# LED.net
KiCad netlist of a schematic drawn in Altium Designer
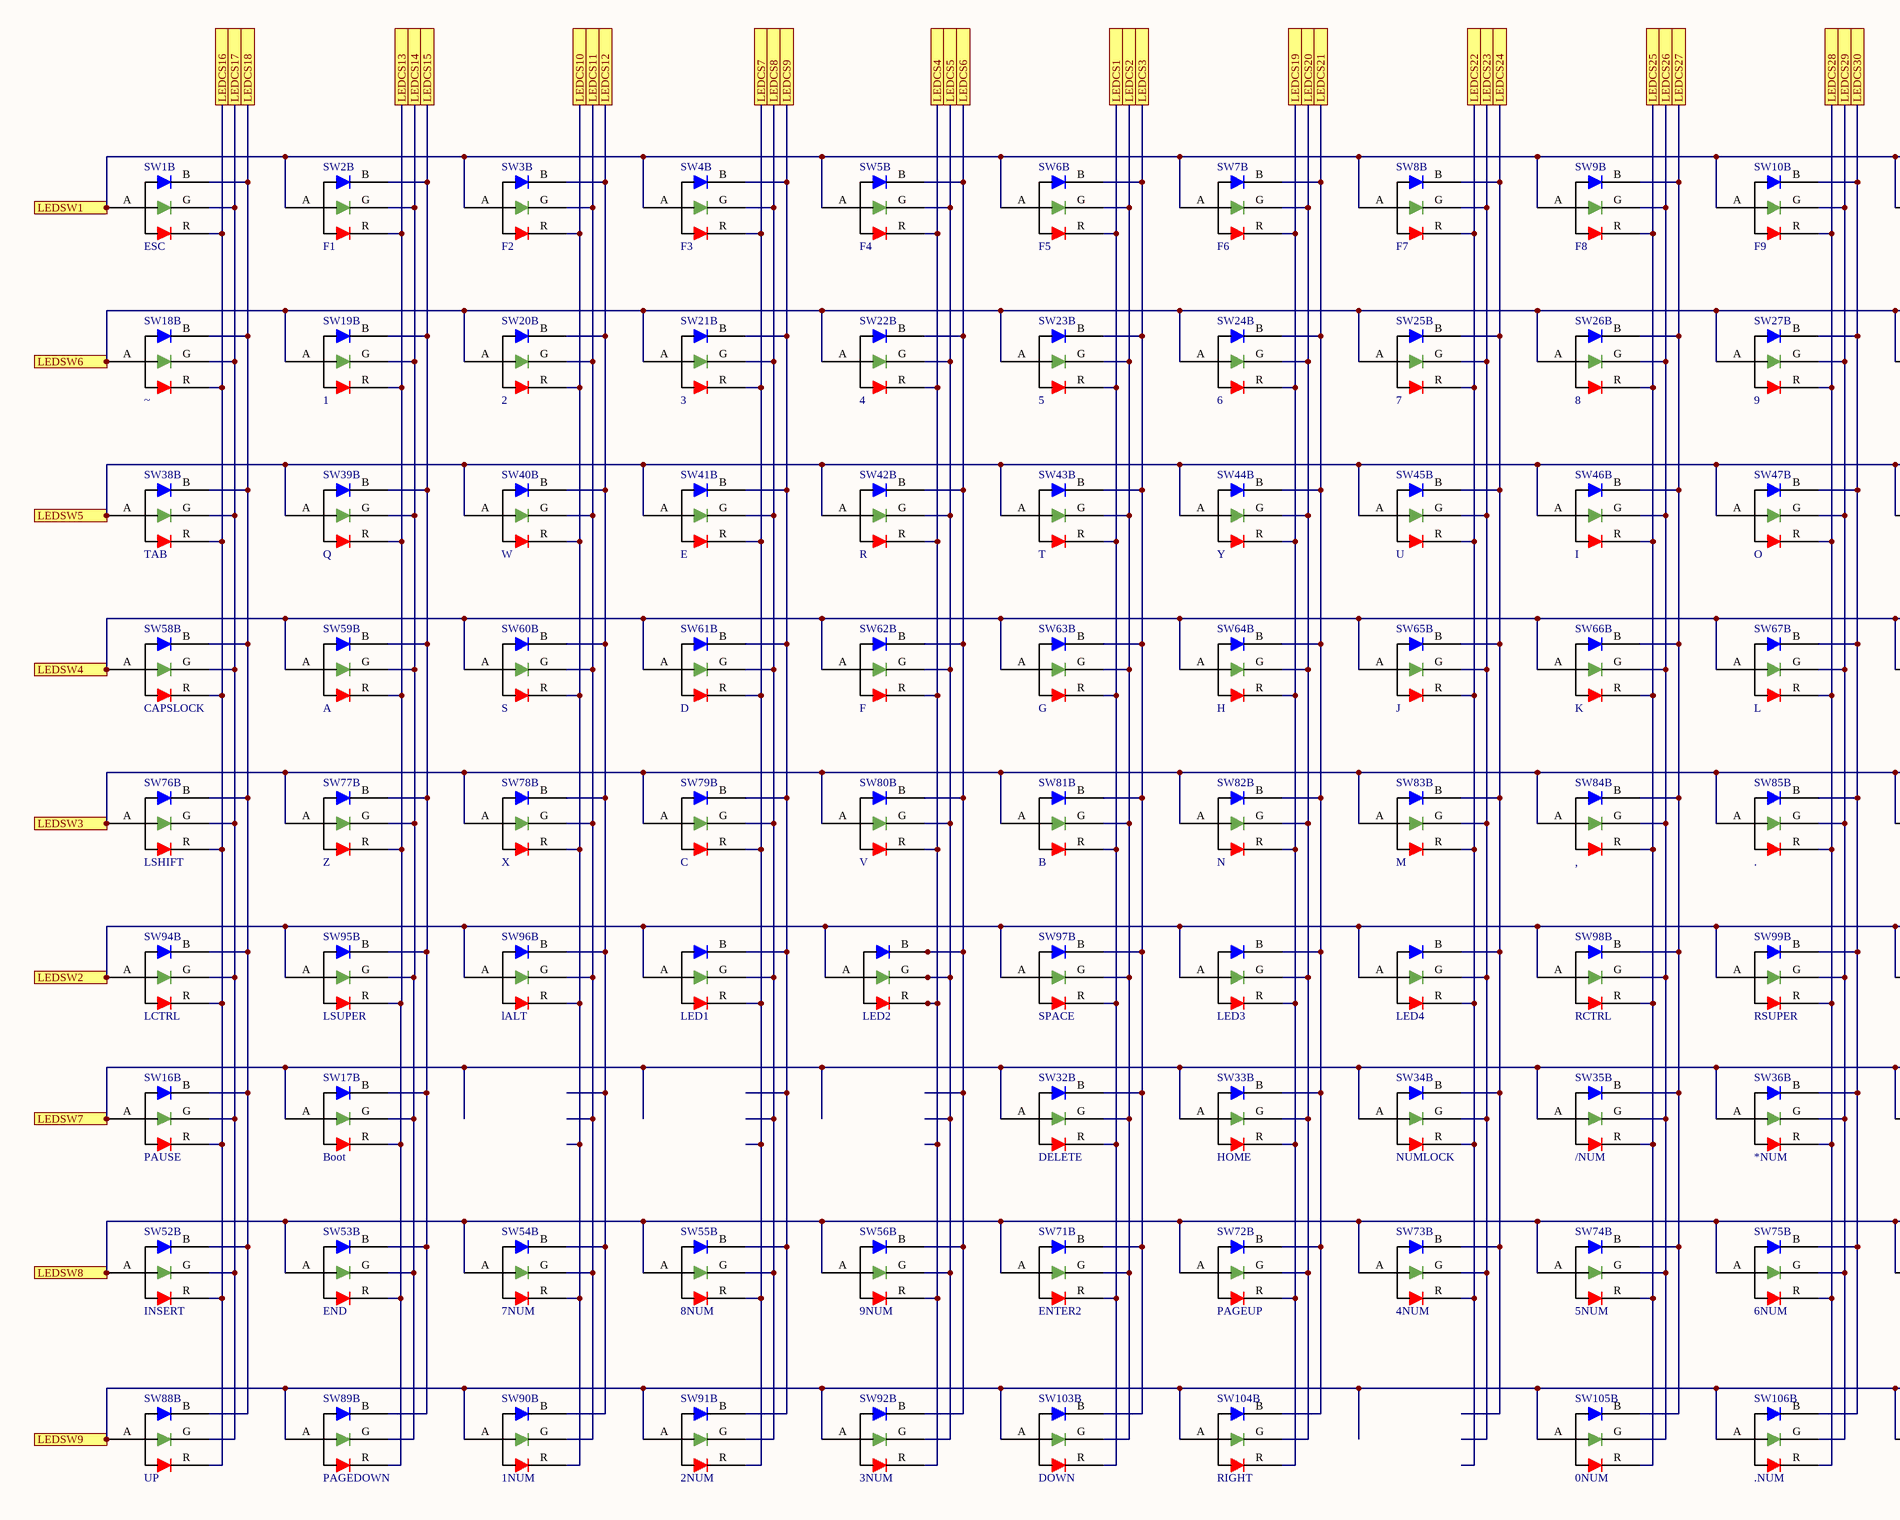
[diagram p0: LED.SchDoc, left]
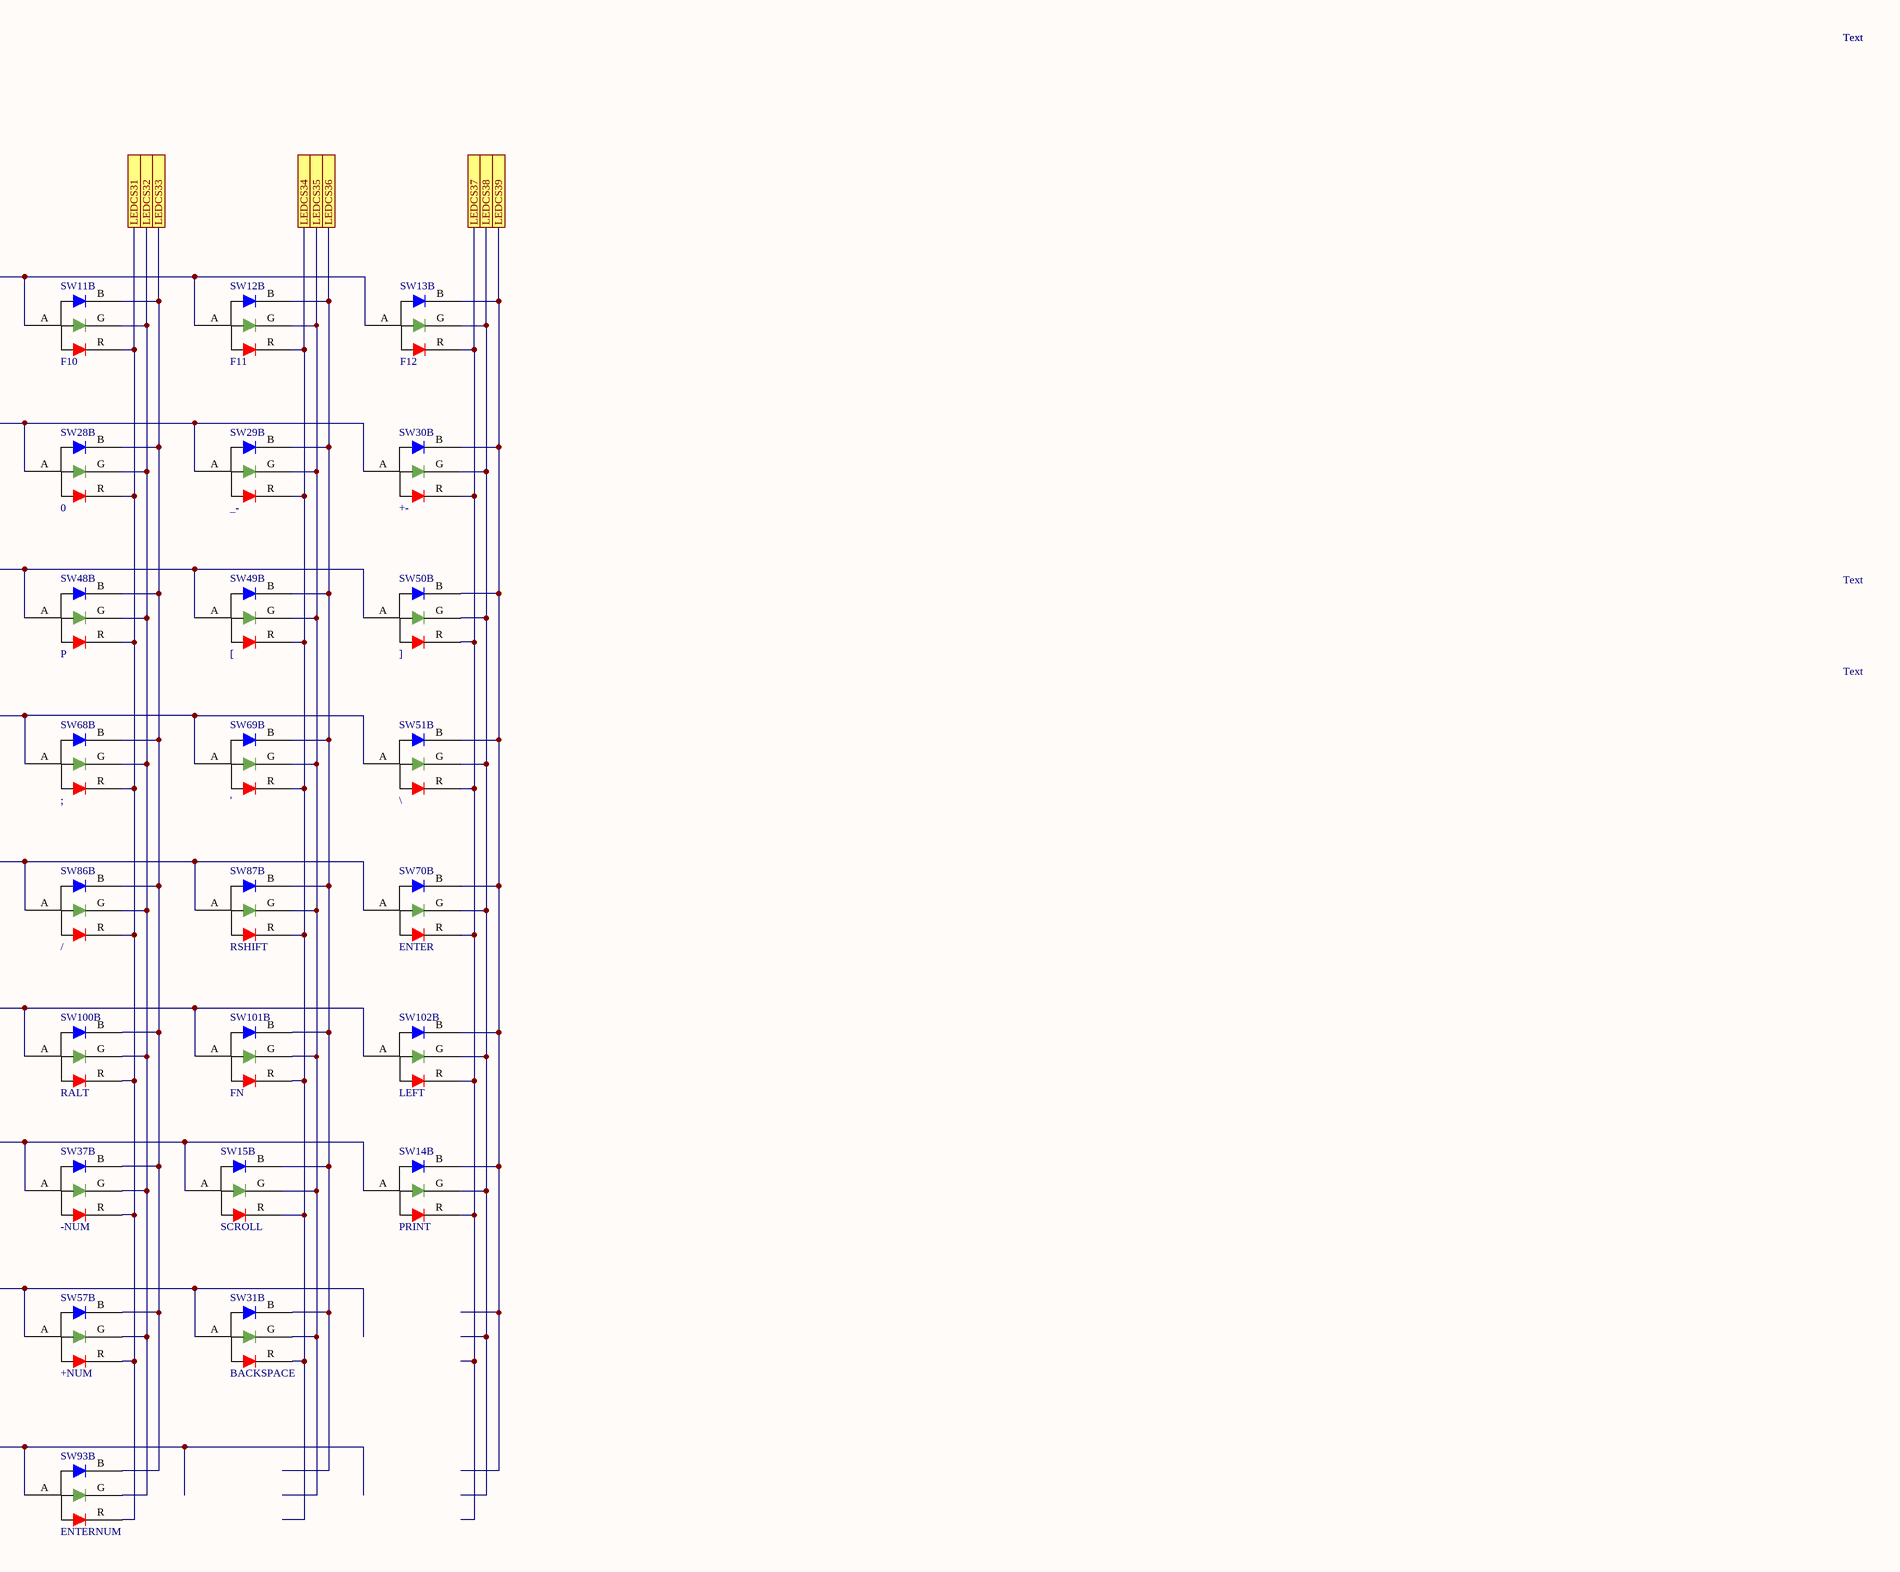
[diagram p1: LED.SchDoc, right]

(export (version "E")
  (design (tool "Eeschema 10.0.6"))
  (components
    (comp (ref "LED1")
      (value "ASMB-MTB0-0A3A2")
      (footprint "smd led")
      (libsource (lib "General") (part "ASMB-MTB0-0A3A2"))
    )
    (comp (ref "LED2")
      (value "ASMB-MTB0-0A3A2")
      (footprint "smd led")
      (libsource (lib "General") (part "ASMB-MTB0-0A3A2"))
    )
    (comp (ref "LED3")
      (value "ASMB-MTB0-0A3A2")
      (footprint "smd led")
      (libsource (lib "General") (part "ASMB-MTB0-0A3A2"))
    )
    (comp (ref "LED4")
      (value "ASMB-MTB0-0A3A2")
      (footprint "smd led")
      (libsource (lib "General") (part "ASMB-MTB0-0A3A2"))
    )
    (comp (ref "SW1")
      (value "ESC")
      (footprint "SWITCH_U1_W_LED")
      (libsource (lib "General") (part "MX_SWITCH_SINGLE_W_SMD_LED"))
    )
    (comp (ref "SW2")
      (value "F1")
      (footprint "SWITCH_U1_W_LED")
      (libsource (lib "General") (part "MX_SWITCH_SINGLE_W_SMD_LED"))
    )
    (comp (ref "SW3")
      (value "F2")
      (footprint "SWITCH_U1_W_LED")
      (libsource (lib "General") (part "MX_SWITCH_SINGLE_W_SMD_LED"))
    )
    (comp (ref "SW4")
      (value "F3")
      (footprint "SWITCH_U1_W_LED")
      (libsource (lib "General") (part "MX_SWITCH_SINGLE_W_SMD_LED"))
    )
    (comp (ref "SW5")
      (value "F4")
      (footprint "SWITCH_U1_W_LED")
      (libsource (lib "General") (part "MX_SWITCH_SINGLE_W_SMD_LED"))
    )
    (comp (ref "SW6")
      (value "F5")
      (footprint "SWITCH_U1_W_LED")
      (libsource (lib "General") (part "MX_SWITCH_SINGLE_W_SMD_LED"))
    )
    (comp (ref "SW7")
      (value "F6")
      (footprint "SWITCH_U1_W_LED")
      (libsource (lib "General") (part "MX_SWITCH_SINGLE_W_SMD_LED"))
    )
    (comp (ref "SW8")
      (value "F7")
      (footprint "SWITCH_U1_W_LED")
      (libsource (lib "General") (part "MX_SWITCH_SINGLE_W_SMD_LED"))
    )
    (comp (ref "SW9")
      (value "F8")
      (footprint "SWITCH_U1_W_LED")
      (libsource (lib "General") (part "MX_SWITCH_SINGLE_W_SMD_LED"))
    )
    (comp (ref "SW10")
      (value "F9")
      (footprint "SWITCH_U1_W_LED")
      (libsource (lib "General") (part "MX_SWITCH_SINGLE_W_SMD_LED"))
    )
    (comp (ref "SW11")
      (value "F10")
      (footprint "SWITCH_U1_W_LED")
      (libsource (lib "General") (part "MX_SWITCH_SINGLE_W_SMD_LED"))
    )
    (comp (ref "SW12")
      (value "F11")
      (footprint "SWITCH_U1_W_LED")
      (libsource (lib "General") (part "MX_SWITCH_SINGLE_W_SMD_LED"))
    )
    (comp (ref "SW13")
      (value "F12")
      (footprint "SWITCH_U1_W_LED")
      (libsource (lib "General") (part "MX_SWITCH_SINGLE_W_SMD_LED"))
    )
    (comp (ref "SW14")
      (value "PRINT")
      (footprint "SWITCH_U1_W_LED")
      (libsource (lib "General") (part "MX_SWITCH_SINGLE_W_SMD_LED"))
    )
    (comp (ref "SW15")
      (value "SCROLL")
      (footprint "SWITCH_U1_W_LED")
      (libsource (lib "General") (part "MX_SWITCH_SINGLE_W_SMD_LED"))
    )
    (comp (ref "SW16")
      (value "PAUSE")
      (footprint "SWITCH_U1_W_LED")
      (libsource (lib "General") (part "MX_SWITCH_SINGLE_W_SMD_LED"))
    )
    (comp (ref "SW17")
      (value "Boot")
      (footprint "SWITCH_U1_W_LED")
      (libsource (lib "General") (part "MX_SWITCH_SINGLE_W_SMD_LED"))
    )
    (comp (ref "SW18")
      (value "~")
      (footprint "SWITCH_U1_W_LED")
      (libsource (lib "General") (part "MX_SWITCH_SINGLE_W_SMD_LED"))
    )
    (comp (ref "SW19")
      (value "1")
      (footprint "SWITCH_U1_W_LED")
      (libsource (lib "General") (part "MX_SWITCH_SINGLE_W_SMD_LED"))
    )
    (comp (ref "SW20")
      (value "2")
      (footprint "SWITCH_U1_W_LED")
      (libsource (lib "General") (part "MX_SWITCH_SINGLE_W_SMD_LED"))
    )
    (comp (ref "SW21")
      (value "3")
      (footprint "SWITCH_U1_W_LED")
      (libsource (lib "General") (part "MX_SWITCH_SINGLE_W_SMD_LED"))
    )
    (comp (ref "SW22")
      (value "4")
      (footprint "SWITCH_U1_W_LED")
      (libsource (lib "General") (part "MX_SWITCH_SINGLE_W_SMD_LED"))
    )
    (comp (ref "SW23")
      (value "5")
      (footprint "SWITCH_U1_W_LED")
      (libsource (lib "General") (part "MX_SWITCH_SINGLE_W_SMD_LED"))
    )
    (comp (ref "SW24")
      (value "6")
      (footprint "SWITCH_U1_W_LED")
      (libsource (lib "General") (part "MX_SWITCH_SINGLE_W_SMD_LED"))
    )
    (comp (ref "SW25")
      (value "7")
      (footprint "SWITCH_U1_W_LED")
      (libsource (lib "General") (part "MX_SWITCH_SINGLE_W_SMD_LED"))
    )
    (comp (ref "SW26")
      (value "8")
      (footprint "SWITCH_U1_W_LED")
      (libsource (lib "General") (part "MX_SWITCH_SINGLE_W_SMD_LED"))
    )
    (comp (ref "SW27")
      (value "9")
      (footprint "SWITCH_U1_W_LED")
      (libsource (lib "General") (part "MX_SWITCH_SINGLE_W_SMD_LED"))
    )
    (comp (ref "SW28")
      (value "0")
      (footprint "SWITCH_U1_W_LED")
      (libsource (lib "General") (part "MX_SWITCH_SINGLE_W_SMD_LED"))
    )
    (comp (ref "SW29")
      (value "_-")
      (footprint "SWITCH_U1_W_LED")
      (libsource (lib "General") (part "MX_SWITCH_SINGLE_W_SMD_LED"))
    )
    (comp (ref "SW30")
      (value "+-")
      (footprint "SWITCH_U1_W_LED")
      (libsource (lib "General") (part "MX_SWITCH_SINGLE_W_SMD_LED"))
    )
    (comp (ref "SW31")
      (value "BACKSPACE")
      (footprint "SWITCH_U2_W_LED")
      (libsource (lib "General") (part "MX_SWITCH_SINGLE_W_SMD_LED"))
    )
    (comp (ref "SW32")
      (value "DELETE")
      (footprint "SWITCH_U1_W_LED")
      (libsource (lib "General") (part "MX_SWITCH_SINGLE_W_SMD_LED"))
    )
    (comp (ref "SW33")
      (value "HOME")
      (footprint "SWITCH_U1_W_LED")
      (libsource (lib "General") (part "MX_SWITCH_SINGLE_W_SMD_LED"))
    )
    (comp (ref "SW34")
      (value "NUMLOCK")
      (footprint "SWITCH_U1_W_LED")
      (libsource (lib "General") (part "MX_SWITCH_SINGLE_W_SMD_LED"))
    )
    (comp (ref "SW35")
      (value "/NUM")
      (footprint "SWITCH_U1_W_LED")
      (libsource (lib "General") (part "MX_SWITCH_SINGLE_W_SMD_LED"))
    )
    (comp (ref "SW36")
      (value "*NUM")
      (footprint "SWITCH_U1_W_LED")
      (libsource (lib "General") (part "MX_SWITCH_SINGLE_W_SMD_LED"))
    )
    (comp (ref "SW37")
      (value "-NUM")
      (footprint "SWITCH_U1_W_LED")
      (libsource (lib "General") (part "MX_SWITCH_SINGLE_W_SMD_LED"))
    )
    (comp (ref "SW38")
      (value "TAB")
      (footprint "SWITCH_U1.50_W_LED")
      (libsource (lib "General") (part "MX_SWITCH_SINGLE_W_SMD_LED"))
    )
    (comp (ref "SW39")
      (value "Q")
      (footprint "SWITCH_U1_W_LED")
      (libsource (lib "General") (part "MX_SWITCH_SINGLE_W_SMD_LED"))
    )
    (comp (ref "SW40")
      (value "W")
      (footprint "SWITCH_U1_W_LED")
      (libsource (lib "General") (part "MX_SWITCH_SINGLE_W_SMD_LED"))
    )
    (comp (ref "SW41")
      (value "E")
      (footprint "SWITCH_U1_W_LED")
      (libsource (lib "General") (part "MX_SWITCH_SINGLE_W_SMD_LED"))
    )
    (comp (ref "SW42")
      (value "R")
      (footprint "SWITCH_U1_W_LED")
      (libsource (lib "General") (part "MX_SWITCH_SINGLE_W_SMD_LED"))
    )
    (comp (ref "SW43")
      (value "T")
      (footprint "SWITCH_U1_W_LED")
      (libsource (lib "General") (part "MX_SWITCH_SINGLE_W_SMD_LED"))
    )
    (comp (ref "SW44")
      (value "Y")
      (footprint "SWITCH_U1_W_LED")
      (libsource (lib "General") (part "MX_SWITCH_SINGLE_W_SMD_LED"))
    )
    (comp (ref "SW45")
      (value "U")
      (footprint "SWITCH_U1_W_LED")
      (libsource (lib "General") (part "MX_SWITCH_SINGLE_W_SMD_LED"))
    )
    (comp (ref "SW46")
      (value "I")
      (footprint "SWITCH_U1_W_LED")
      (libsource (lib "General") (part "MX_SWITCH_SINGLE_W_SMD_LED"))
    )
    (comp (ref "SW47")
      (value "O")
      (footprint "SWITCH_U1_W_LED")
      (libsource (lib "General") (part "MX_SWITCH_SINGLE_W_SMD_LED"))
    )
    (comp (ref "SW48")
      (value "P")
      (footprint "SWITCH_U1_W_LED")
      (libsource (lib "General") (part "MX_SWITCH_SINGLE_W_SMD_LED"))
    )
    (comp (ref "SW49")
      (value "[")
      (footprint "SWITCH_U1_W_LED")
      (libsource (lib "General") (part "MX_SWITCH_SINGLE_W_SMD_LED"))
    )
    (comp (ref "SW50")
      (value "]")
      (footprint "SWITCH_U1_W_LED")
      (libsource (lib "General") (part "MX_SWITCH_SINGLE_W_SMD_LED"))
    )
    (comp (ref "SW51")
      (value "\\")
      (footprint "SWITCH_U1.50_W_LED")
      (libsource (lib "General") (part "MX_SWITCH_SINGLE_W_SMD_LED"))
    )
    (comp (ref "SW52")
      (value "INSERT")
      (footprint "SWITCH_U1_W_LED")
      (libsource (lib "General") (part "MX_SWITCH_SINGLE_W_SMD_LED"))
    )
    (comp (ref "SW53")
      (value "END")
      (footprint "SWITCH_U1_W_LED")
      (libsource (lib "General") (part "MX_SWITCH_SINGLE_W_SMD_LED"))
    )
    (comp (ref "SW54")
      (value "7NUM")
      (footprint "SWITCH_U1_W_LED")
      (libsource (lib "General") (part "MX_SWITCH_SINGLE_W_SMD_LED"))
    )
    (comp (ref "SW55")
      (value "8NUM")
      (footprint "SWITCH_U1_W_LED")
      (libsource (lib "General") (part "MX_SWITCH_SINGLE_W_SMD_LED"))
    )
    (comp (ref "SW56")
      (value "9NUM")
      (footprint "SWITCH_U1_W_LED")
      (libsource (lib "General") (part "MX_SWITCH_SINGLE_W_SMD_LED"))
    )
    (comp (ref "SW57")
      (value "+NUM")
      (footprint "SWITCH_U2_W_LED - vert")
      (libsource (lib "General") (part "MX_SWITCH_SINGLE_W_SMD_LED"))
    )
    (comp (ref "SW58")
      (value "CAPSLOCK")
      (footprint "SWITCH_U1.75_W_LED")
      (libsource (lib "General") (part "MX_SWITCH_SINGLE_W_SMD_LED"))
    )
    (comp (ref "SW59")
      (value "A")
      (footprint "SWITCH_U1_W_LED")
      (libsource (lib "General") (part "MX_SWITCH_SINGLE_W_SMD_LED"))
    )
    (comp (ref "SW60")
      (value "S")
      (footprint "SWITCH_U1_W_LED")
      (libsource (lib "General") (part "MX_SWITCH_SINGLE_W_SMD_LED"))
    )
    (comp (ref "SW61")
      (value "D")
      (footprint "SWITCH_U1_W_LED")
      (libsource (lib "General") (part "MX_SWITCH_SINGLE_W_SMD_LED"))
    )
    (comp (ref "SW62")
      (value "F")
      (footprint "SWITCH_U1_W_LED")
      (libsource (lib "General") (part "MX_SWITCH_SINGLE_W_SMD_LED"))
    )
    (comp (ref "SW63")
      (value "G")
      (footprint "SWITCH_U1_W_LED")
      (libsource (lib "General") (part "MX_SWITCH_SINGLE_W_SMD_LED"))
    )
    (comp (ref "SW64")
      (value "H")
      (footprint "SWITCH_U1_W_LED")
      (libsource (lib "General") (part "MX_SWITCH_SINGLE_W_SMD_LED"))
    )
    (comp (ref "SW65")
      (value "J")
      (footprint "SWITCH_U1_W_LED")
      (libsource (lib "General") (part "MX_SWITCH_SINGLE_W_SMD_LED"))
    )
    (comp (ref "SW66")
      (value "K")
      (footprint "SWITCH_U1_W_LED")
      (libsource (lib "General") (part "MX_SWITCH_SINGLE_W_SMD_LED"))
    )
    (comp (ref "SW67")
      (value "L")
      (footprint "SWITCH_U1_W_LED")
      (libsource (lib "General") (part "MX_SWITCH_SINGLE_W_SMD_LED"))
    )
    (comp (ref "SW68")
      (value ";")
      (footprint "SWITCH_U1_W_LED")
      (libsource (lib "General") (part "MX_SWITCH_SINGLE_W_SMD_LED"))
    )
    (comp (ref "SW69")
      (value "'")
      (footprint "SWITCH_U1_W_LED")
      (libsource (lib "General") (part "MX_SWITCH_SINGLE_W_SMD_LED"))
    )
    (comp (ref "SW70")
      (value "ENTER")
      (footprint "SWITCH_U2.25_W_LED")
      (libsource (lib "General") (part "MX_SWITCH_SINGLE_W_SMD_LED"))
    )
    (comp (ref "SW71")
      (value "ENTER2")
      (footprint "SWITCH_U1_W_LED")
      (libsource (lib "General") (part "MX_SWITCH_SINGLE_W_SMD_LED"))
    )
    (comp (ref "SW72")
      (value "PAGEUP")
      (footprint "SWITCH_U1_W_LED")
      (libsource (lib "General") (part "MX_SWITCH_SINGLE_W_SMD_LED"))
    )
    (comp (ref "SW73")
      (value "4NUM")
      (footprint "SWITCH_U1_W_LED")
      (libsource (lib "General") (part "MX_SWITCH_SINGLE_W_SMD_LED"))
    )
    (comp (ref "SW74")
      (value "5NUM")
      (footprint "SWITCH_U1_W_LED")
      (libsource (lib "General") (part "MX_SWITCH_SINGLE_W_SMD_LED"))
    )
    (comp (ref "SW75")
      (value "6NUM")
      (footprint "SWITCH_U1_W_LED")
      (libsource (lib "General") (part "MX_SWITCH_SINGLE_W_SMD_LED"))
    )
    (comp (ref "SW76")
      (value "LSHIFT")
      (footprint "SWITCH_U2.25_W_LED")
      (libsource (lib "General") (part "MX_SWITCH_SINGLE_W_SMD_LED"))
    )
    (comp (ref "SW77")
      (value "Z")
      (footprint "SWITCH_U1_W_LED")
      (libsource (lib "General") (part "MX_SWITCH_SINGLE_W_SMD_LED"))
    )
    (comp (ref "SW78")
      (value "X")
      (footprint "SWITCH_U1_W_LED")
      (libsource (lib "General") (part "MX_SWITCH_SINGLE_W_SMD_LED"))
    )
    (comp (ref "SW79")
      (value "C")
      (footprint "SWITCH_U1_W_LED")
      (libsource (lib "General") (part "MX_SWITCH_SINGLE_W_SMD_LED"))
    )
    (comp (ref "SW80")
      (value "V")
      (footprint "SWITCH_U1_W_LED")
      (libsource (lib "General") (part "MX_SWITCH_SINGLE_W_SMD_LED"))
    )
    (comp (ref "SW81")
      (value "B")
      (footprint "SWITCH_U1_W_LED")
      (libsource (lib "General") (part "MX_SWITCH_SINGLE_W_SMD_LED"))
    )
    (comp (ref "SW82")
      (value "N")
      (footprint "SWITCH_U1_W_LED")
      (libsource (lib "General") (part "MX_SWITCH_SINGLE_W_SMD_LED"))
    )
    (comp (ref "SW83")
      (value "M")
      (footprint "SWITCH_U1_W_LED")
      (libsource (lib "General") (part "MX_SWITCH_SINGLE_W_SMD_LED"))
    )
    (comp (ref "SW84")
      (value ",")
      (footprint "SWITCH_U1_W_LED")
      (libsource (lib "General") (part "MX_SWITCH_SINGLE_W_SMD_LED"))
    )
    (comp (ref "SW85")
      (value ".")
      (footprint "SWITCH_U1_W_LED")
      (libsource (lib "General") (part "MX_SWITCH_SINGLE_W_SMD_LED"))
    )
    (comp (ref "SW86")
      (value "/")
      (footprint "SWITCH_U1_W_LED")
      (libsource (lib "General") (part "MX_SWITCH_SINGLE_W_SMD_LED"))
    )
    (comp (ref "SW87")
      (value "RSHIFT")
      (footprint "SWITCH_U2.75_W_LED")
      (libsource (lib "General") (part "MX_SWITCH_SINGLE_W_SMD_LED"))
    )
    (comp (ref "SW88")
      (value "UP")
      (footprint "SWITCH_U1_W_LED")
      (libsource (lib "General") (part "MX_SWITCH_SINGLE_W_SMD_LED"))
    )
    (comp (ref "SW89")
      (value "PAGEDOWN")
      (footprint "SWITCH_U1_W_LED")
      (libsource (lib "General") (part "MX_SWITCH_SINGLE_W_SMD_LED"))
    )
    (comp (ref "SW90")
      (value "1NUM")
      (footprint "SWITCH_U1_W_LED")
      (libsource (lib "General") (part "MX_SWITCH_SINGLE_W_SMD_LED"))
    )
    (comp (ref "SW91")
      (value "2NUM")
      (footprint "SWITCH_U1_W_LED")
      (libsource (lib "General") (part "MX_SWITCH_SINGLE_W_SMD_LED"))
    )
    (comp (ref "SW92")
      (value "3NUM")
      (footprint "SWITCH_U1_W_LED")
      (libsource (lib "General") (part "MX_SWITCH_SINGLE_W_SMD_LED"))
    )
    (comp (ref "SW93")
      (value "ENTERNUM")
      (footprint "SWITCH_U2_W_LED - vert")
      (libsource (lib "General") (part "MX_SWITCH_SINGLE_W_SMD_LED"))
    )
    (comp (ref "SW94")
      (value "LCTRL")
      (footprint "SWITCH_U1.25_W_LED")
      (libsource (lib "General") (part "MX_SWITCH_SINGLE_W_SMD_LED"))
    )
    (comp (ref "SW95")
      (value "LSUPER")
      (footprint "SWITCH_U1.25_W_LED")
      (libsource (lib "General") (part "MX_SWITCH_SINGLE_W_SMD_LED"))
    )
    (comp (ref "SW96")
      (value "lALT")
      (footprint "SWITCH_U1.25_W_LED")
      (libsource (lib "General") (part "MX_SWITCH_SINGLE_W_SMD_LED"))
    )
    (comp (ref "SW97")
      (value "SPACE")
      (footprint "SWITCH_U6.25_W_LED - duplicate")
      (libsource (lib "General") (part "MX_SWITCH_SINGLE_W_SMD_LED"))
    )
    (comp (ref "SW98")
      (value "RCTRL")
      (footprint "SWITCH_U1_W_LED")
      (libsource (lib "General") (part "MX_SWITCH_SINGLE_W_SMD_LED"))
    )
    (comp (ref "SW99")
      (value "RSUPER")
      (footprint "SWITCH_U1_W_LED")
      (libsource (lib "General") (part "MX_SWITCH_SINGLE_W_SMD_LED"))
    )
    (comp (ref "SW100")
      (value "RALT")
      (footprint "SWITCH_U1_W_LED")
      (libsource (lib "General") (part "MX_SWITCH_SINGLE_W_SMD_LED"))
    )
    (comp (ref "SW101")
      (value "FN")
      (footprint "SWITCH_U1_W_LED")
      (libsource (lib "General") (part "MX_SWITCH_SINGLE_W_SMD_LED"))
    )
    (comp (ref "SW102")
      (value "LEFT")
      (footprint "SWITCH_U1_W_LED")
      (libsource (lib "General") (part "MX_SWITCH_SINGLE_W_SMD_LED"))
    )
    (comp (ref "SW103")
      (value "DOWN")
      (footprint "SWITCH_U1_W_LED")
      (libsource (lib "General") (part "MX_SWITCH_SINGLE_W_SMD_LED"))
    )
    (comp (ref "SW104")
      (value "RIGHT")
      (footprint "SWITCH_U1_W_LED")
      (libsource (lib "General") (part "MX_SWITCH_SINGLE_W_SMD_LED"))
    )
    (comp (ref "SW105")
      (value "0NUM")
      (footprint "SWITCH_U2_W_LED")
      (libsource (lib "General") (part "MX_SWITCH_SINGLE_W_SMD_LED"))
    )
    (comp (ref "SW106")
      (value ".NUM")
      (footprint "SWITCH_U1_W_LED")
      (libsource (lib "General") (part "MX_SWITCH_SINGLE_W_SMD_LED"))
    )
  )
  (nets
    (net (code "1") (name "/LEDCS1") (class "Default")
      (node (ref "SW103") (pin "R") (pinfunction "R_R") (pintype "passive"))
      (node (ref "SW23") (pin "R") (pinfunction "R_R") (pintype "passive"))
      (node (ref "SW32") (pin "R") (pinfunction "R_R") (pintype "passive"))
      (node (ref "SW43") (pin "R") (pinfunction "R_R") (pintype "passive"))
      (node (ref "SW6") (pin "R") (pinfunction "R_R") (pintype "passive"))
      (node (ref "SW63") (pin "R") (pinfunction "R_R") (pintype "passive"))
      (node (ref "SW71") (pin "R") (pinfunction "R_R") (pintype "passive"))
      (node (ref "SW81") (pin "R") (pinfunction "R_R") (pintype "passive"))
      (node (ref "SW97") (pin "R") (pinfunction "R_R") (pintype "passive"))
    )
    (net (code "2") (name "/LEDCS2") (class "Default")
      (node (ref "SW103") (pin "G") (pinfunction "G_G") (pintype "passive"))
      (node (ref "SW23") (pin "G") (pinfunction "G_G") (pintype "passive"))
      (node (ref "SW32") (pin "G") (pinfunction "G_G") (pintype "passive"))
      (node (ref "SW43") (pin "G") (pinfunction "G_G") (pintype "passive"))
      (node (ref "SW6") (pin "G") (pinfunction "G_G") (pintype "passive"))
      (node (ref "SW63") (pin "G") (pinfunction "G_G") (pintype "passive"))
      (node (ref "SW71") (pin "G") (pinfunction "G_G") (pintype "passive"))
      (node (ref "SW81") (pin "G") (pinfunction "G_G") (pintype "passive"))
      (node (ref "SW97") (pin "G") (pinfunction "G_G") (pintype "passive"))
    )
    (net (code "3") (name "/LEDCS3") (class "Default")
      (node (ref "SW103") (pin "B") (pinfunction "B_B") (pintype "passive"))
      (node (ref "SW23") (pin "B") (pinfunction "B_B") (pintype "passive"))
      (node (ref "SW32") (pin "B") (pinfunction "B_B") (pintype "passive"))
      (node (ref "SW43") (pin "B") (pinfunction "B_B") (pintype "passive"))
      (node (ref "SW6") (pin "B") (pinfunction "B_B") (pintype "passive"))
      (node (ref "SW63") (pin "B") (pinfunction "B_B") (pintype "passive"))
      (node (ref "SW71") (pin "B") (pinfunction "B_B") (pintype "passive"))
      (node (ref "SW81") (pin "B") (pinfunction "B_B") (pintype "passive"))
      (node (ref "SW97") (pin "B") (pinfunction "B_B") (pintype "passive"))
    )
    (net (code "4") (name "/LEDCS4") (class "Default")
      (node (ref "LED2") (pin "R") (pinfunction "R_R") (pintype "passive"))
      (node (ref "SW22") (pin "R") (pinfunction "R_R") (pintype "passive"))
      (node (ref "SW42") (pin "R") (pinfunction "R_R") (pintype "passive"))
      (node (ref "SW5") (pin "R") (pinfunction "R_R") (pintype "passive"))
      (node (ref "SW56") (pin "R") (pinfunction "R_R") (pintype "passive"))
      (node (ref "SW62") (pin "R") (pinfunction "R_R") (pintype "passive"))
      (node (ref "SW80") (pin "R") (pinfunction "R_R") (pintype "passive"))
      (node (ref "SW92") (pin "R") (pinfunction "R_R") (pintype "passive"))
    )
    (net (code "5") (name "/LEDCS5") (class "Default")
      (node (ref "LED2") (pin "G") (pinfunction "G_G") (pintype "passive"))
      (node (ref "SW22") (pin "G") (pinfunction "G_G") (pintype "passive"))
      (node (ref "SW42") (pin "G") (pinfunction "G_G") (pintype "passive"))
      (node (ref "SW5") (pin "G") (pinfunction "G_G") (pintype "passive"))
      (node (ref "SW56") (pin "G") (pinfunction "G_G") (pintype "passive"))
      (node (ref "SW62") (pin "G") (pinfunction "G_G") (pintype "passive"))
      (node (ref "SW80") (pin "G") (pinfunction "G_G") (pintype "passive"))
      (node (ref "SW92") (pin "G") (pinfunction "G_G") (pintype "passive"))
    )
    (net (code "6") (name "/LEDCS6") (class "Default")
      (node (ref "LED2") (pin "B") (pinfunction "B_B") (pintype "passive"))
      (node (ref "SW22") (pin "B") (pinfunction "B_B") (pintype "passive"))
      (node (ref "SW42") (pin "B") (pinfunction "B_B") (pintype "passive"))
      (node (ref "SW5") (pin "B") (pinfunction "B_B") (pintype "passive"))
      (node (ref "SW56") (pin "B") (pinfunction "B_B") (pintype "passive"))
      (node (ref "SW62") (pin "B") (pinfunction "B_B") (pintype "passive"))
      (node (ref "SW80") (pin "B") (pinfunction "B_B") (pintype "passive"))
      (node (ref "SW92") (pin "B") (pinfunction "B_B") (pintype "passive"))
    )
    (net (code "7") (name "/LEDCS7") (class "Default")
      (node (ref "LED1") (pin "R") (pinfunction "R_R") (pintype "passive"))
      (node (ref "SW21") (pin "R") (pinfunction "R_R") (pintype "passive"))
      (node (ref "SW4") (pin "R") (pinfunction "R_R") (pintype "passive"))
      (node (ref "SW41") (pin "R") (pinfunction "R_R") (pintype "passive"))
      (node (ref "SW55") (pin "R") (pinfunction "R_R") (pintype "passive"))
      (node (ref "SW61") (pin "R") (pinfunction "R_R") (pintype "passive"))
      (node (ref "SW79") (pin "R") (pinfunction "R_R") (pintype "passive"))
      (node (ref "SW91") (pin "R") (pinfunction "R_R") (pintype "passive"))
    )
    (net (code "8") (name "/LEDCS8") (class "Default")
      (node (ref "LED1") (pin "G") (pinfunction "G_G") (pintype "passive"))
      (node (ref "SW21") (pin "G") (pinfunction "G_G") (pintype "passive"))
      (node (ref "SW4") (pin "G") (pinfunction "G_G") (pintype "passive"))
      (node (ref "SW41") (pin "G") (pinfunction "G_G") (pintype "passive"))
      (node (ref "SW55") (pin "G") (pinfunction "G_G") (pintype "passive"))
      (node (ref "SW61") (pin "G") (pinfunction "G_G") (pintype "passive"))
      (node (ref "SW79") (pin "G") (pinfunction "G_G") (pintype "passive"))
      (node (ref "SW91") (pin "G") (pinfunction "G_G") (pintype "passive"))
    )
    (net (code "9") (name "/LEDCS9") (class "Default")
      (node (ref "LED1") (pin "B") (pinfunction "B_B") (pintype "passive"))
      (node (ref "SW21") (pin "B") (pinfunction "B_B") (pintype "passive"))
      (node (ref "SW4") (pin "B") (pinfunction "B_B") (pintype "passive"))
      (node (ref "SW41") (pin "B") (pinfunction "B_B") (pintype "passive"))
      (node (ref "SW55") (pin "B") (pinfunction "B_B") (pintype "passive"))
      (node (ref "SW61") (pin "B") (pinfunction "B_B") (pintype "passive"))
      (node (ref "SW79") (pin "B") (pinfunction "B_B") (pintype "passive"))
      (node (ref "SW91") (pin "B") (pinfunction "B_B") (pintype "passive"))
    )
    (net (code "10") (name "/LEDCS10") (class "Default")
      (node (ref "SW20") (pin "R") (pinfunction "R_R") (pintype "passive"))
      (node (ref "SW3") (pin "R") (pinfunction "R_R") (pintype "passive"))
      (node (ref "SW40") (pin "R") (pinfunction "R_R") (pintype "passive"))
      (node (ref "SW54") (pin "R") (pinfunction "R_R") (pintype "passive"))
      (node (ref "SW60") (pin "R") (pinfunction "R_R") (pintype "passive"))
      (node (ref "SW78") (pin "R") (pinfunction "R_R") (pintype "passive"))
      (node (ref "SW90") (pin "R") (pinfunction "R_R") (pintype "passive"))
      (node (ref "SW96") (pin "R") (pinfunction "R_R") (pintype "passive"))
    )
    (net (code "11") (name "/LEDCS11") (class "Default")
      (node (ref "SW20") (pin "G") (pinfunction "G_G") (pintype "passive"))
      (node (ref "SW3") (pin "G") (pinfunction "G_G") (pintype "passive"))
      (node (ref "SW40") (pin "G") (pinfunction "G_G") (pintype "passive"))
      (node (ref "SW54") (pin "G") (pinfunction "G_G") (pintype "passive"))
      (node (ref "SW60") (pin "G") (pinfunction "G_G") (pintype "passive"))
      (node (ref "SW78") (pin "G") (pinfunction "G_G") (pintype "passive"))
      (node (ref "SW90") (pin "G") (pinfunction "G_G") (pintype "passive"))
      (node (ref "SW96") (pin "G") (pinfunction "G_G") (pintype "passive"))
    )
    (net (code "12") (name "/LEDCS12") (class "Default")
      (node (ref "SW20") (pin "B") (pinfunction "B_B") (pintype "passive"))
      (node (ref "SW3") (pin "B") (pinfunction "B_B") (pintype "passive"))
      (node (ref "SW40") (pin "B") (pinfunction "B_B") (pintype "passive"))
      (node (ref "SW54") (pin "B") (pinfunction "B_B") (pintype "passive"))
      (node (ref "SW60") (pin "B") (pinfunction "B_B") (pintype "passive"))
      (node (ref "SW78") (pin "B") (pinfunction "B_B") (pintype "passive"))
      (node (ref "SW90") (pin "B") (pinfunction "B_B") (pintype "passive"))
      (node (ref "SW96") (pin "B") (pinfunction "B_B") (pintype "passive"))
    )
    (net (code "13") (name "/LEDCS13") (class "Default")
      (node (ref "SW17") (pin "R") (pinfunction "R_R") (pintype "passive"))
      (node (ref "SW19") (pin "R") (pinfunction "R_R") (pintype "passive"))
      (node (ref "SW2") (pin "R") (pinfunction "R_R") (pintype "passive"))
      (node (ref "SW39") (pin "R") (pinfunction "R_R") (pintype "passive"))
      (node (ref "SW53") (pin "R") (pinfunction "R_R") (pintype "passive"))
      (node (ref "SW59") (pin "R") (pinfunction "R_R") (pintype "passive"))
      (node (ref "SW77") (pin "R") (pinfunction "R_R") (pintype "passive"))
      (node (ref "SW89") (pin "R") (pinfunction "R_R") (pintype "passive"))
      (node (ref "SW95") (pin "R") (pinfunction "R_R") (pintype "passive"))
    )
    (net (code "14") (name "/LEDCS14") (class "Default")
      (node (ref "SW17") (pin "G") (pinfunction "G_G") (pintype "passive"))
      (node (ref "SW19") (pin "G") (pinfunction "G_G") (pintype "passive"))
      (node (ref "SW2") (pin "G") (pinfunction "G_G") (pintype "passive"))
      (node (ref "SW39") (pin "G") (pinfunction "G_G") (pintype "passive"))
      (node (ref "SW53") (pin "G") (pinfunction "G_G") (pintype "passive"))
      (node (ref "SW59") (pin "G") (pinfunction "G_G") (pintype "passive"))
      (node (ref "SW77") (pin "G") (pinfunction "G_G") (pintype "passive"))
      (node (ref "SW89") (pin "G") (pinfunction "G_G") (pintype "passive"))
      (node (ref "SW95") (pin "G") (pinfunction "G_G") (pintype "passive"))
    )
    (net (code "15") (name "/LEDCS15") (class "Default")
      (node (ref "SW17") (pin "B") (pinfunction "B_B") (pintype "passive"))
      (node (ref "SW19") (pin "B") (pinfunction "B_B") (pintype "passive"))
      (node (ref "SW2") (pin "B") (pinfunction "B_B") (pintype "passive"))
      (node (ref "SW39") (pin "B") (pinfunction "B_B") (pintype "passive"))
      (node (ref "SW53") (pin "B") (pinfunction "B_B") (pintype "passive"))
      (node (ref "SW59") (pin "B") (pinfunction "B_B") (pintype "passive"))
      (node (ref "SW77") (pin "B") (pinfunction "B_B") (pintype "passive"))
      (node (ref "SW89") (pin "B") (pinfunction "B_B") (pintype "passive"))
      (node (ref "SW95") (pin "B") (pinfunction "B_B") (pintype "passive"))
    )
    (net (code "16") (name "/LEDCS16") (class "Default")
      (node (ref "SW1") (pin "R") (pinfunction "R_R") (pintype "passive"))
      (node (ref "SW16") (pin "R") (pinfunction "R_R") (pintype "passive"))
      (node (ref "SW18") (pin "R") (pinfunction "R_R") (pintype "passive"))
      (node (ref "SW38") (pin "R") (pinfunction "R_R") (pintype "passive"))
      (node (ref "SW52") (pin "R") (pinfunction "R_R") (pintype "passive"))
      (node (ref "SW58") (pin "R") (pinfunction "R_R") (pintype "passive"))
      (node (ref "SW76") (pin "R") (pinfunction "R_R") (pintype "passive"))
      (node (ref "SW88") (pin "R") (pinfunction "R_R") (pintype "passive"))
      (node (ref "SW94") (pin "R") (pinfunction "R_R") (pintype "passive"))
    )
    (net (code "17") (name "/LEDCS17") (class "Default")
      (node (ref "SW1") (pin "G") (pinfunction "G_G") (pintype "passive"))
      (node (ref "SW16") (pin "G") (pinfunction "G_G") (pintype "passive"))
      (node (ref "SW18") (pin "G") (pinfunction "G_G") (pintype "passive"))
      (node (ref "SW38") (pin "G") (pinfunction "G_G") (pintype "passive"))
      (node (ref "SW52") (pin "G") (pinfunction "G_G") (pintype "passive"))
      (node (ref "SW58") (pin "G") (pinfunction "G_G") (pintype "passive"))
      (node (ref "SW76") (pin "G") (pinfunction "G_G") (pintype "passive"))
      (node (ref "SW88") (pin "G") (pinfunction "G_G") (pintype "passive"))
      (node (ref "SW94") (pin "G") (pinfunction "G_G") (pintype "passive"))
    )
    (net (code "18") (name "/LEDCS18") (class "Default")
      (node (ref "SW1") (pin "B") (pinfunction "B_B") (pintype "passive"))
      (node (ref "SW16") (pin "B") (pinfunction "B_B") (pintype "passive"))
      (node (ref "SW18") (pin "B") (pinfunction "B_B") (pintype "passive"))
      (node (ref "SW38") (pin "B") (pinfunction "B_B") (pintype "passive"))
      (node (ref "SW52") (pin "B") (pinfunction "B_B") (pintype "passive"))
      (node (ref "SW58") (pin "B") (pinfunction "B_B") (pintype "passive"))
      (node (ref "SW76") (pin "B") (pinfunction "B_B") (pintype "passive"))
      (node (ref "SW88") (pin "B") (pinfunction "B_B") (pintype "passive"))
      (node (ref "SW94") (pin "B") (pinfunction "B_B") (pintype "passive"))
    )
    (net (code "19") (name "/LEDCS19") (class "Default")
      (node (ref "LED3") (pin "R") (pinfunction "R_R") (pintype "passive"))
      (node (ref "SW104") (pin "R") (pinfunction "R_R") (pintype "passive"))
      (node (ref "SW24") (pin "R") (pinfunction "R_R") (pintype "passive"))
      (node (ref "SW33") (pin "R") (pinfunction "R_R") (pintype "passive"))
      (node (ref "SW44") (pin "R") (pinfunction "R_R") (pintype "passive"))
      (node (ref "SW64") (pin "R") (pinfunction "R_R") (pintype "passive"))
      (node (ref "SW7") (pin "R") (pinfunction "R_R") (pintype "passive"))
      (node (ref "SW72") (pin "R") (pinfunction "R_R") (pintype "passive"))
      (node (ref "SW82") (pin "R") (pinfunction "R_R") (pintype "passive"))
    )
    (net (code "20") (name "/LEDCS20") (class "Default")
      (node (ref "LED3") (pin "G") (pinfunction "G_G") (pintype "passive"))
      (node (ref "SW104") (pin "G") (pinfunction "G_G") (pintype "passive"))
      (node (ref "SW24") (pin "G") (pinfunction "G_G") (pintype "passive"))
      (node (ref "SW33") (pin "G") (pinfunction "G_G") (pintype "passive"))
      (node (ref "SW44") (pin "G") (pinfunction "G_G") (pintype "passive"))
      (node (ref "SW64") (pin "G") (pinfunction "G_G") (pintype "passive"))
      (node (ref "SW7") (pin "G") (pinfunction "G_G") (pintype "passive"))
      (node (ref "SW72") (pin "G") (pinfunction "G_G") (pintype "passive"))
      (node (ref "SW82") (pin "G") (pinfunction "G_G") (pintype "passive"))
    )
    (net (code "21") (name "/LEDCS21") (class "Default")
      (node (ref "LED3") (pin "B") (pinfunction "B_B") (pintype "passive"))
      (node (ref "SW104") (pin "B") (pinfunction "B_B") (pintype "passive"))
      (node (ref "SW24") (pin "B") (pinfunction "B_B") (pintype "passive"))
      (node (ref "SW33") (pin "B") (pinfunction "B_B") (pintype "passive"))
      (node (ref "SW44") (pin "B") (pinfunction "B_B") (pintype "passive"))
      (node (ref "SW64") (pin "B") (pinfunction "B_B") (pintype "passive"))
      (node (ref "SW7") (pin "B") (pinfunction "B_B") (pintype "passive"))
      (node (ref "SW72") (pin "B") (pinfunction "B_B") (pintype "passive"))
      (node (ref "SW82") (pin "B") (pinfunction "B_B") (pintype "passive"))
    )
    (net (code "22") (name "/LEDCS22") (class "Default")
      (node (ref "LED4") (pin "R") (pinfunction "R_R") (pintype "passive"))
      (node (ref "SW25") (pin "R") (pinfunction "R_R") (pintype "passive"))
      (node (ref "SW34") (pin "R") (pinfunction "R_R") (pintype "passive"))
      (node (ref "SW45") (pin "R") (pinfunction "R_R") (pintype "passive"))
      (node (ref "SW65") (pin "R") (pinfunction "R_R") (pintype "passive"))
      (node (ref "SW73") (pin "R") (pinfunction "R_R") (pintype "passive"))
      (node (ref "SW8") (pin "R") (pinfunction "R_R") (pintype "passive"))
      (node (ref "SW83") (pin "R") (pinfunction "R_R") (pintype "passive"))
    )
    (net (code "23") (name "/LEDCS23") (class "Default")
      (node (ref "LED4") (pin "G") (pinfunction "G_G") (pintype "passive"))
      (node (ref "SW25") (pin "G") (pinfunction "G_G") (pintype "passive"))
      (node (ref "SW34") (pin "G") (pinfunction "G_G") (pintype "passive"))
      (node (ref "SW45") (pin "G") (pinfunction "G_G") (pintype "passive"))
      (node (ref "SW65") (pin "G") (pinfunction "G_G") (pintype "passive"))
      (node (ref "SW73") (pin "G") (pinfunction "G_G") (pintype "passive"))
      (node (ref "SW8") (pin "G") (pinfunction "G_G") (pintype "passive"))
      (node (ref "SW83") (pin "G") (pinfunction "G_G") (pintype "passive"))
    )
    (net (code "24") (name "/LEDCS24") (class "Default")
      (node (ref "LED4") (pin "B") (pinfunction "B_B") (pintype "passive"))
      (node (ref "SW25") (pin "B") (pinfunction "B_B") (pintype "passive"))
      (node (ref "SW34") (pin "B") (pinfunction "B_B") (pintype "passive"))
      (node (ref "SW45") (pin "B") (pinfunction "B_B") (pintype "passive"))
      (node (ref "SW65") (pin "B") (pinfunction "B_B") (pintype "passive"))
      (node (ref "SW73") (pin "B") (pinfunction "B_B") (pintype "passive"))
      (node (ref "SW8") (pin "B") (pinfunction "B_B") (pintype "passive"))
      (node (ref "SW83") (pin "B") (pinfunction "B_B") (pintype "passive"))
    )
    (net (code "25") (name "/LEDCS25") (class "Default")
      (node (ref "SW105") (pin "R") (pinfunction "R_R") (pintype "passive"))
      (node (ref "SW26") (pin "R") (pinfunction "R_R") (pintype "passive"))
      (node (ref "SW35") (pin "R") (pinfunction "R_R") (pintype "passive"))
      (node (ref "SW46") (pin "R") (pinfunction "R_R") (pintype "passive"))
      (node (ref "SW66") (pin "R") (pinfunction "R_R") (pintype "passive"))
      (node (ref "SW74") (pin "R") (pinfunction "R_R") (pintype "passive"))
      (node (ref "SW84") (pin "R") (pinfunction "R_R") (pintype "passive"))
      (node (ref "SW9") (pin "R") (pinfunction "R_R") (pintype "passive"))
      (node (ref "SW98") (pin "R") (pinfunction "R_R") (pintype "passive"))
    )
    (net (code "26") (name "/LEDCS26") (class "Default")
      (node (ref "SW105") (pin "G") (pinfunction "G_G") (pintype "passive"))
      (node (ref "SW26") (pin "G") (pinfunction "G_G") (pintype "passive"))
      (node (ref "SW35") (pin "G") (pinfunction "G_G") (pintype "passive"))
      (node (ref "SW46") (pin "G") (pinfunction "G_G") (pintype "passive"))
      (node (ref "SW66") (pin "G") (pinfunction "G_G") (pintype "passive"))
      (node (ref "SW74") (pin "G") (pinfunction "G_G") (pintype "passive"))
      (node (ref "SW84") (pin "G") (pinfunction "G_G") (pintype "passive"))
      (node (ref "SW9") (pin "G") (pinfunction "G_G") (pintype "passive"))
      (node (ref "SW98") (pin "G") (pinfunction "G_G") (pintype "passive"))
    )
    (net (code "27") (name "/LEDCS27") (class "Default")
      (node (ref "SW105") (pin "B") (pinfunction "B_B") (pintype "passive"))
      (node (ref "SW26") (pin "B") (pinfunction "B_B") (pintype "passive"))
      (node (ref "SW35") (pin "B") (pinfunction "B_B") (pintype "passive"))
      (node (ref "SW46") (pin "B") (pinfunction "B_B") (pintype "passive"))
      (node (ref "SW66") (pin "B") (pinfunction "B_B") (pintype "passive"))
      (node (ref "SW74") (pin "B") (pinfunction "B_B") (pintype "passive"))
      (node (ref "SW84") (pin "B") (pinfunction "B_B") (pintype "passive"))
      (node (ref "SW9") (pin "B") (pinfunction "B_B") (pintype "passive"))
      (node (ref "SW98") (pin "B") (pinfunction "B_B") (pintype "passive"))
    )
    (net (code "28") (name "/LEDCS28") (class "Default")
      (node (ref "SW10") (pin "R") (pinfunction "R_R") (pintype "passive"))
      (node (ref "SW106") (pin "R") (pinfunction "R_R") (pintype "passive"))
      (node (ref "SW27") (pin "R") (pinfunction "R_R") (pintype "passive"))
      (node (ref "SW36") (pin "R") (pinfunction "R_R") (pintype "passive"))
      (node (ref "SW47") (pin "R") (pinfunction "R_R") (pintype "passive"))
      (node (ref "SW67") (pin "R") (pinfunction "R_R") (pintype "passive"))
      (node (ref "SW75") (pin "R") (pinfunction "R_R") (pintype "passive"))
      (node (ref "SW85") (pin "R") (pinfunction "R_R") (pintype "passive"))
      (node (ref "SW99") (pin "R") (pinfunction "R_R") (pintype "passive"))
    )
    (net (code "29") (name "/LEDCS29") (class "Default")
      (node (ref "SW10") (pin "G") (pinfunction "G_G") (pintype "passive"))
      (node (ref "SW106") (pin "G") (pinfunction "G_G") (pintype "passive"))
      (node (ref "SW27") (pin "G") (pinfunction "G_G") (pintype "passive"))
      (node (ref "SW36") (pin "G") (pinfunction "G_G") (pintype "passive"))
      (node (ref "SW47") (pin "G") (pinfunction "G_G") (pintype "passive"))
      (node (ref "SW67") (pin "G") (pinfunction "G_G") (pintype "passive"))
      (node (ref "SW75") (pin "G") (pinfunction "G_G") (pintype "passive"))
      (node (ref "SW85") (pin "G") (pinfunction "G_G") (pintype "passive"))
      (node (ref "SW99") (pin "G") (pinfunction "G_G") (pintype "passive"))
    )
    (net (code "30") (name "/LEDCS30") (class "Default")
      (node (ref "SW10") (pin "B") (pinfunction "B_B") (pintype "passive"))
      (node (ref "SW106") (pin "B") (pinfunction "B_B") (pintype "passive"))
      (node (ref "SW27") (pin "B") (pinfunction "B_B") (pintype "passive"))
      (node (ref "SW36") (pin "B") (pinfunction "B_B") (pintype "passive"))
      (node (ref "SW47") (pin "B") (pinfunction "B_B") (pintype "passive"))
      (node (ref "SW67") (pin "B") (pinfunction "B_B") (pintype "passive"))
      (node (ref "SW75") (pin "B") (pinfunction "B_B") (pintype "passive"))
      (node (ref "SW85") (pin "B") (pinfunction "B_B") (pintype "passive"))
      (node (ref "SW99") (pin "B") (pinfunction "B_B") (pintype "passive"))
    )
    (net (code "31") (name "/LEDCS31") (class "Default")
      (node (ref "SW100") (pin "R") (pinfunction "R_R") (pintype "passive"))
      (node (ref "SW11") (pin "R") (pinfunction "R_R") (pintype "passive"))
      (node (ref "SW28") (pin "R") (pinfunction "R_R") (pintype "passive"))
      (node (ref "SW37") (pin "R") (pinfunction "R_R") (pintype "passive"))
      (node (ref "SW48") (pin "R") (pinfunction "R_R") (pintype "passive"))
      (node (ref "SW57") (pin "R") (pinfunction "R_R") (pintype "passive"))
      (node (ref "SW68") (pin "R") (pinfunction "R_R") (pintype "passive"))
      (node (ref "SW86") (pin "R") (pinfunction "R_R") (pintype "passive"))
      (node (ref "SW93") (pin "R") (pinfunction "R_R") (pintype "passive"))
    )
    (net (code "32") (name "/LEDCS32") (class "Default")
      (node (ref "SW100") (pin "G") (pinfunction "G_G") (pintype "passive"))
      (node (ref "SW11") (pin "G") (pinfunction "G_G") (pintype "passive"))
      (node (ref "SW28") (pin "G") (pinfunction "G_G") (pintype "passive"))
      (node (ref "SW37") (pin "G") (pinfunction "G_G") (pintype "passive"))
      (node (ref "SW48") (pin "G") (pinfunction "G_G") (pintype "passive"))
      (node (ref "SW57") (pin "G") (pinfunction "G_G") (pintype "passive"))
      (node (ref "SW68") (pin "G") (pinfunction "G_G") (pintype "passive"))
      (node (ref "SW86") (pin "G") (pinfunction "G_G") (pintype "passive"))
      (node (ref "SW93") (pin "G") (pinfunction "G_G") (pintype "passive"))
    )
    (net (code "33") (name "/LEDCS33") (class "Default")
      (node (ref "SW100") (pin "B") (pinfunction "B_B") (pintype "passive"))
      (node (ref "SW11") (pin "B") (pinfunction "B_B") (pintype "passive"))
      (node (ref "SW28") (pin "B") (pinfunction "B_B") (pintype "passive"))
      (node (ref "SW37") (pin "B") (pinfunction "B_B") (pintype "passive"))
      (node (ref "SW48") (pin "B") (pinfunction "B_B") (pintype "passive"))
      (node (ref "SW57") (pin "B") (pinfunction "B_B") (pintype "passive"))
      (node (ref "SW68") (pin "B") (pinfunction "B_B") (pintype "passive"))
      (node (ref "SW86") (pin "B") (pinfunction "B_B") (pintype "passive"))
      (node (ref "SW93") (pin "B") (pinfunction "B_B") (pintype "passive"))
    )
    (net (code "34") (name "/LEDCS34") (class "Default")
      (node (ref "SW101") (pin "R") (pinfunction "R_R") (pintype "passive"))
      (node (ref "SW12") (pin "R") (pinfunction "R_R") (pintype "passive"))
      (node (ref "SW15") (pin "R") (pinfunction "R_R") (pintype "passive"))
      (node (ref "SW29") (pin "R") (pinfunction "R_R") (pintype "passive"))
      (node (ref "SW31") (pin "R") (pinfunction "R_R") (pintype "passive"))
      (node (ref "SW49") (pin "R") (pinfunction "R_R") (pintype "passive"))
      (node (ref "SW69") (pin "R") (pinfunction "R_R") (pintype "passive"))
      (node (ref "SW87") (pin "R") (pinfunction "R_R") (pintype "passive"))
    )
    (net (code "35") (name "/LEDCS35") (class "Default")
      (node (ref "SW101") (pin "G") (pinfunction "G_G") (pintype "passive"))
      (node (ref "SW12") (pin "G") (pinfunction "G_G") (pintype "passive"))
      (node (ref "SW15") (pin "G") (pinfunction "G_G") (pintype "passive"))
      (node (ref "SW29") (pin "G") (pinfunction "G_G") (pintype "passive"))
      (node (ref "SW31") (pin "G") (pinfunction "G_G") (pintype "passive"))
      (node (ref "SW49") (pin "G") (pinfunction "G_G") (pintype "passive"))
      (node (ref "SW69") (pin "G") (pinfunction "G_G") (pintype "passive"))
      (node (ref "SW87") (pin "G") (pinfunction "G_G") (pintype "passive"))
    )
    (net (code "36") (name "/LEDCS36") (class "Default")
      (node (ref "SW101") (pin "B") (pinfunction "B_B") (pintype "passive"))
      (node (ref "SW12") (pin "B") (pinfunction "B_B") (pintype "passive"))
      (node (ref "SW15") (pin "B") (pinfunction "B_B") (pintype "passive"))
      (node (ref "SW29") (pin "B") (pinfunction "B_B") (pintype "passive"))
      (node (ref "SW31") (pin "B") (pinfunction "B_B") (pintype "passive"))
      (node (ref "SW49") (pin "B") (pinfunction "B_B") (pintype "passive"))
      (node (ref "SW69") (pin "B") (pinfunction "B_B") (pintype "passive"))
      (node (ref "SW87") (pin "B") (pinfunction "B_B") (pintype "passive"))
    )
    (net (code "37") (name "/LEDCS37") (class "Default")
      (node (ref "SW102") (pin "R") (pinfunction "R_R") (pintype "passive"))
      (node (ref "SW13") (pin "R") (pinfunction "R_R") (pintype "passive"))
      (node (ref "SW14") (pin "R") (pinfunction "R_R") (pintype "passive"))
      (node (ref "SW30") (pin "R") (pinfunction "R_R") (pintype "passive"))
      (node (ref "SW50") (pin "R") (pinfunction "R_R") (pintype "passive"))
      (node (ref "SW51") (pin "R") (pinfunction "R_R") (pintype "passive"))
      (node (ref "SW70") (pin "R") (pinfunction "R_R") (pintype "passive"))
    )
    (net (code "38") (name "/LEDCS38") (class "Default")
      (node (ref "SW102") (pin "G") (pinfunction "G_G") (pintype "passive"))
      (node (ref "SW13") (pin "G") (pinfunction "G_G") (pintype "passive"))
      (node (ref "SW14") (pin "G") (pinfunction "G_G") (pintype "passive"))
      (node (ref "SW30") (pin "G") (pinfunction "G_G") (pintype "passive"))
      (node (ref "SW50") (pin "G") (pinfunction "G_G") (pintype "passive"))
      (node (ref "SW51") (pin "G") (pinfunction "G_G") (pintype "passive"))
      (node (ref "SW70") (pin "G") (pinfunction "G_G") (pintype "passive"))
    )
    (net (code "39") (name "/LEDCS39") (class "Default")
      (node (ref "SW102") (pin "B") (pinfunction "B_B") (pintype "passive"))
      (node (ref "SW13") (pin "B") (pinfunction "B_B") (pintype "passive"))
      (node (ref "SW14") (pin "B") (pinfunction "B_B") (pintype "passive"))
      (node (ref "SW30") (pin "B") (pinfunction "B_B") (pintype "passive"))
      (node (ref "SW50") (pin "B") (pinfunction "B_B") (pintype "passive"))
      (node (ref "SW51") (pin "B") (pinfunction "B_B") (pintype "passive"))
      (node (ref "SW70") (pin "B") (pinfunction "B_B") (pintype "passive"))
    )
    (net (code "40") (name "/LEDSW1") (class "Default")
      (node (ref "SW1") (pin "A") (pinfunction "A_A") (pintype "passive"))
      (node (ref "SW10") (pin "A") (pinfunction "A_A") (pintype "passive"))
      (node (ref "SW11") (pin "A") (pinfunction "A_A") (pintype "passive"))
      (node (ref "SW12") (pin "A") (pinfunction "A_A") (pintype "passive"))
      (node (ref "SW13") (pin "A") (pinfunction "A_A") (pintype "passive"))
      (node (ref "SW2") (pin "A") (pinfunction "A_A") (pintype "passive"))
      (node (ref "SW3") (pin "A") (pinfunction "A_A") (pintype "passive"))
      (node (ref "SW4") (pin "A") (pinfunction "A_A") (pintype "passive"))
      (node (ref "SW5") (pin "A") (pinfunction "A_A") (pintype "passive"))
      (node (ref "SW6") (pin "A") (pinfunction "A_A") (pintype "passive"))
      (node (ref "SW7") (pin "A") (pinfunction "A_A") (pintype "passive"))
      (node (ref "SW8") (pin "A") (pinfunction "A_A") (pintype "passive"))
      (node (ref "SW9") (pin "A") (pinfunction "A_A") (pintype "passive"))
    )
    (net (code "41") (name "/LEDSW2") (class "Default")
      (node (ref "LED1") (pin "A") (pinfunction "A_A") (pintype "passive"))
      (node (ref "LED2") (pin "A") (pinfunction "A_A") (pintype "passive"))
      (node (ref "LED3") (pin "A") (pinfunction "A_A") (pintype "passive"))
      (node (ref "LED4") (pin "A") (pinfunction "A_A") (pintype "passive"))
      (node (ref "SW100") (pin "A") (pinfunction "A_A") (pintype "passive"))
      (node (ref "SW101") (pin "A") (pinfunction "A_A") (pintype "passive"))
      (node (ref "SW102") (pin "A") (pinfunction "A_A") (pintype "passive"))
      (node (ref "SW94") (pin "A") (pinfunction "A_A") (pintype "passive"))
      (node (ref "SW95") (pin "A") (pinfunction "A_A") (pintype "passive"))
      (node (ref "SW96") (pin "A") (pinfunction "A_A") (pintype "passive"))
      (node (ref "SW97") (pin "A") (pinfunction "A_A") (pintype "passive"))
      (node (ref "SW98") (pin "A") (pinfunction "A_A") (pintype "passive"))
      (node (ref "SW99") (pin "A") (pinfunction "A_A") (pintype "passive"))
    )
    (net (code "42") (name "/LEDSW3") (class "Default")
      (node (ref "SW70") (pin "A") (pinfunction "A_A") (pintype "passive"))
      (node (ref "SW76") (pin "A") (pinfunction "A_A") (pintype "passive"))
      (node (ref "SW77") (pin "A") (pinfunction "A_A") (pintype "passive"))
      (node (ref "SW78") (pin "A") (pinfunction "A_A") (pintype "passive"))
      (node (ref "SW79") (pin "A") (pinfunction "A_A") (pintype "passive"))
      (node (ref "SW80") (pin "A") (pinfunction "A_A") (pintype "passive"))
      (node (ref "SW81") (pin "A") (pinfunction "A_A") (pintype "passive"))
      (node (ref "SW82") (pin "A") (pinfunction "A_A") (pintype "passive"))
      (node (ref "SW83") (pin "A") (pinfunction "A_A") (pintype "passive"))
      (node (ref "SW84") (pin "A") (pinfunction "A_A") (pintype "passive"))
      (node (ref "SW85") (pin "A") (pinfunction "A_A") (pintype "passive"))
      (node (ref "SW86") (pin "A") (pinfunction "A_A") (pintype "passive"))
      (node (ref "SW87") (pin "A") (pinfunction "A_A") (pintype "passive"))
    )
    (net (code "43") (name "/LEDSW4") (class "Default")
      (node (ref "SW51") (pin "A") (pinfunction "A_A") (pintype "passive"))
      (node (ref "SW58") (pin "A") (pinfunction "A_A") (pintype "passive"))
      (node (ref "SW59") (pin "A") (pinfunction "A_A") (pintype "passive"))
      (node (ref "SW60") (pin "A") (pinfunction "A_A") (pintype "passive"))
      (node (ref "SW61") (pin "A") (pinfunction "A_A") (pintype "passive"))
      (node (ref "SW62") (pin "A") (pinfunction "A_A") (pintype "passive"))
      (node (ref "SW63") (pin "A") (pinfunction "A_A") (pintype "passive"))
      (node (ref "SW64") (pin "A") (pinfunction "A_A") (pintype "passive"))
      (node (ref "SW65") (pin "A") (pinfunction "A_A") (pintype "passive"))
      (node (ref "SW66") (pin "A") (pinfunction "A_A") (pintype "passive"))
      (node (ref "SW67") (pin "A") (pinfunction "A_A") (pintype "passive"))
      (node (ref "SW68") (pin "A") (pinfunction "A_A") (pintype "passive"))
      (node (ref "SW69") (pin "A") (pinfunction "A_A") (pintype "passive"))
    )
    (net (code "44") (name "/LEDSW5") (class "Default")
      (node (ref "SW38") (pin "A") (pinfunction "A_A") (pintype "passive"))
      (node (ref "SW39") (pin "A") (pinfunction "A_A") (pintype "passive"))
      (node (ref "SW40") (pin "A") (pinfunction "A_A") (pintype "passive"))
      (node (ref "SW41") (pin "A") (pinfunction "A_A") (pintype "passive"))
      (node (ref "SW42") (pin "A") (pinfunction "A_A") (pintype "passive"))
      (node (ref "SW43") (pin "A") (pinfunction "A_A") (pintype "passive"))
      (node (ref "SW44") (pin "A") (pinfunction "A_A") (pintype "passive"))
      (node (ref "SW45") (pin "A") (pinfunction "A_A") (pintype "passive"))
      (node (ref "SW46") (pin "A") (pinfunction "A_A") (pintype "passive"))
      (node (ref "SW47") (pin "A") (pinfunction "A_A") (pintype "passive"))
      (node (ref "SW48") (pin "A") (pinfunction "A_A") (pintype "passive"))
      (node (ref "SW49") (pin "A") (pinfunction "A_A") (pintype "passive"))
      (node (ref "SW50") (pin "A") (pinfunction "A_A") (pintype "passive"))
    )
    (net (code "45") (name "/LEDSW6") (class "Default")
      (node (ref "SW18") (pin "A") (pinfunction "A_A") (pintype "passive"))
      (node (ref "SW19") (pin "A") (pinfunction "A_A") (pintype "passive"))
      (node (ref "SW20") (pin "A") (pinfunction "A_A") (pintype "passive"))
      (node (ref "SW21") (pin "A") (pinfunction "A_A") (pintype "passive"))
      (node (ref "SW22") (pin "A") (pinfunction "A_A") (pintype "passive"))
      (node (ref "SW23") (pin "A") (pinfunction "A_A") (pintype "passive"))
      (node (ref "SW24") (pin "A") (pinfunction "A_A") (pintype "passive"))
      (node (ref "SW25") (pin "A") (pinfunction "A_A") (pintype "passive"))
      (node (ref "SW26") (pin "A") (pinfunction "A_A") (pintype "passive"))
      (node (ref "SW27") (pin "A") (pinfunction "A_A") (pintype "passive"))
      (node (ref "SW28") (pin "A") (pinfunction "A_A") (pintype "passive"))
      (node (ref "SW29") (pin "A") (pinfunction "A_A") (pintype "passive"))
      (node (ref "SW30") (pin "A") (pinfunction "A_A") (pintype "passive"))
    )
    (net (code "46") (name "/LEDSW7") (class "Default")
      (node (ref "SW14") (pin "A") (pinfunction "A_A") (pintype "passive"))
      (node (ref "SW15") (pin "A") (pinfunction "A_A") (pintype "passive"))
      (node (ref "SW16") (pin "A") (pinfunction "A_A") (pintype "passive"))
      (node (ref "SW17") (pin "A") (pinfunction "A_A") (pintype "passive"))
      (node (ref "SW32") (pin "A") (pinfunction "A_A") (pintype "passive"))
      (node (ref "SW33") (pin "A") (pinfunction "A_A") (pintype "passive"))
      (node (ref "SW34") (pin "A") (pinfunction "A_A") (pintype "passive"))
      (node (ref "SW35") (pin "A") (pinfunction "A_A") (pintype "passive"))
      (node (ref "SW36") (pin "A") (pinfunction "A_A") (pintype "passive"))
      (node (ref "SW37") (pin "A") (pinfunction "A_A") (pintype "passive"))
    )
    (net (code "47") (name "/LEDSW8") (class "Default")
      (node (ref "SW31") (pin "A") (pinfunction "A_A") (pintype "passive"))
      (node (ref "SW52") (pin "A") (pinfunction "A_A") (pintype "passive"))
      (node (ref "SW53") (pin "A") (pinfunction "A_A") (pintype "passive"))
      (node (ref "SW54") (pin "A") (pinfunction "A_A") (pintype "passive"))
      (node (ref "SW55") (pin "A") (pinfunction "A_A") (pintype "passive"))
      (node (ref "SW56") (pin "A") (pinfunction "A_A") (pintype "passive"))
      (node (ref "SW57") (pin "A") (pinfunction "A_A") (pintype "passive"))
      (node (ref "SW71") (pin "A") (pinfunction "A_A") (pintype "passive"))
      (node (ref "SW72") (pin "A") (pinfunction "A_A") (pintype "passive"))
      (node (ref "SW73") (pin "A") (pinfunction "A_A") (pintype "passive"))
      (node (ref "SW74") (pin "A") (pinfunction "A_A") (pintype "passive"))
      (node (ref "SW75") (pin "A") (pinfunction "A_A") (pintype "passive"))
    )
    (net (code "48") (name "/LEDSW9") (class "Default")
      (node (ref "SW103") (pin "A") (pinfunction "A_A") (pintype "passive"))
      (node (ref "SW104") (pin "A") (pinfunction "A_A") (pintype "passive"))
      (node (ref "SW105") (pin "A") (pinfunction "A_A") (pintype "passive"))
      (node (ref "SW106") (pin "A") (pinfunction "A_A") (pintype "passive"))
      (node (ref "SW88") (pin "A") (pinfunction "A_A") (pintype "passive"))
      (node (ref "SW89") (pin "A") (pinfunction "A_A") (pintype "passive"))
      (node (ref "SW90") (pin "A") (pinfunction "A_A") (pintype "passive"))
      (node (ref "SW91") (pin "A") (pinfunction "A_A") (pintype "passive"))
      (node (ref "SW92") (pin "A") (pinfunction "A_A") (pintype "passive"))
      (node (ref "SW93") (pin "A") (pinfunction "A_A") (pintype "passive"))
    )
  )
)
